# SparkFun_Noisy_Cricket.net
KiCad netlist of a schematic drawn in EAGLE
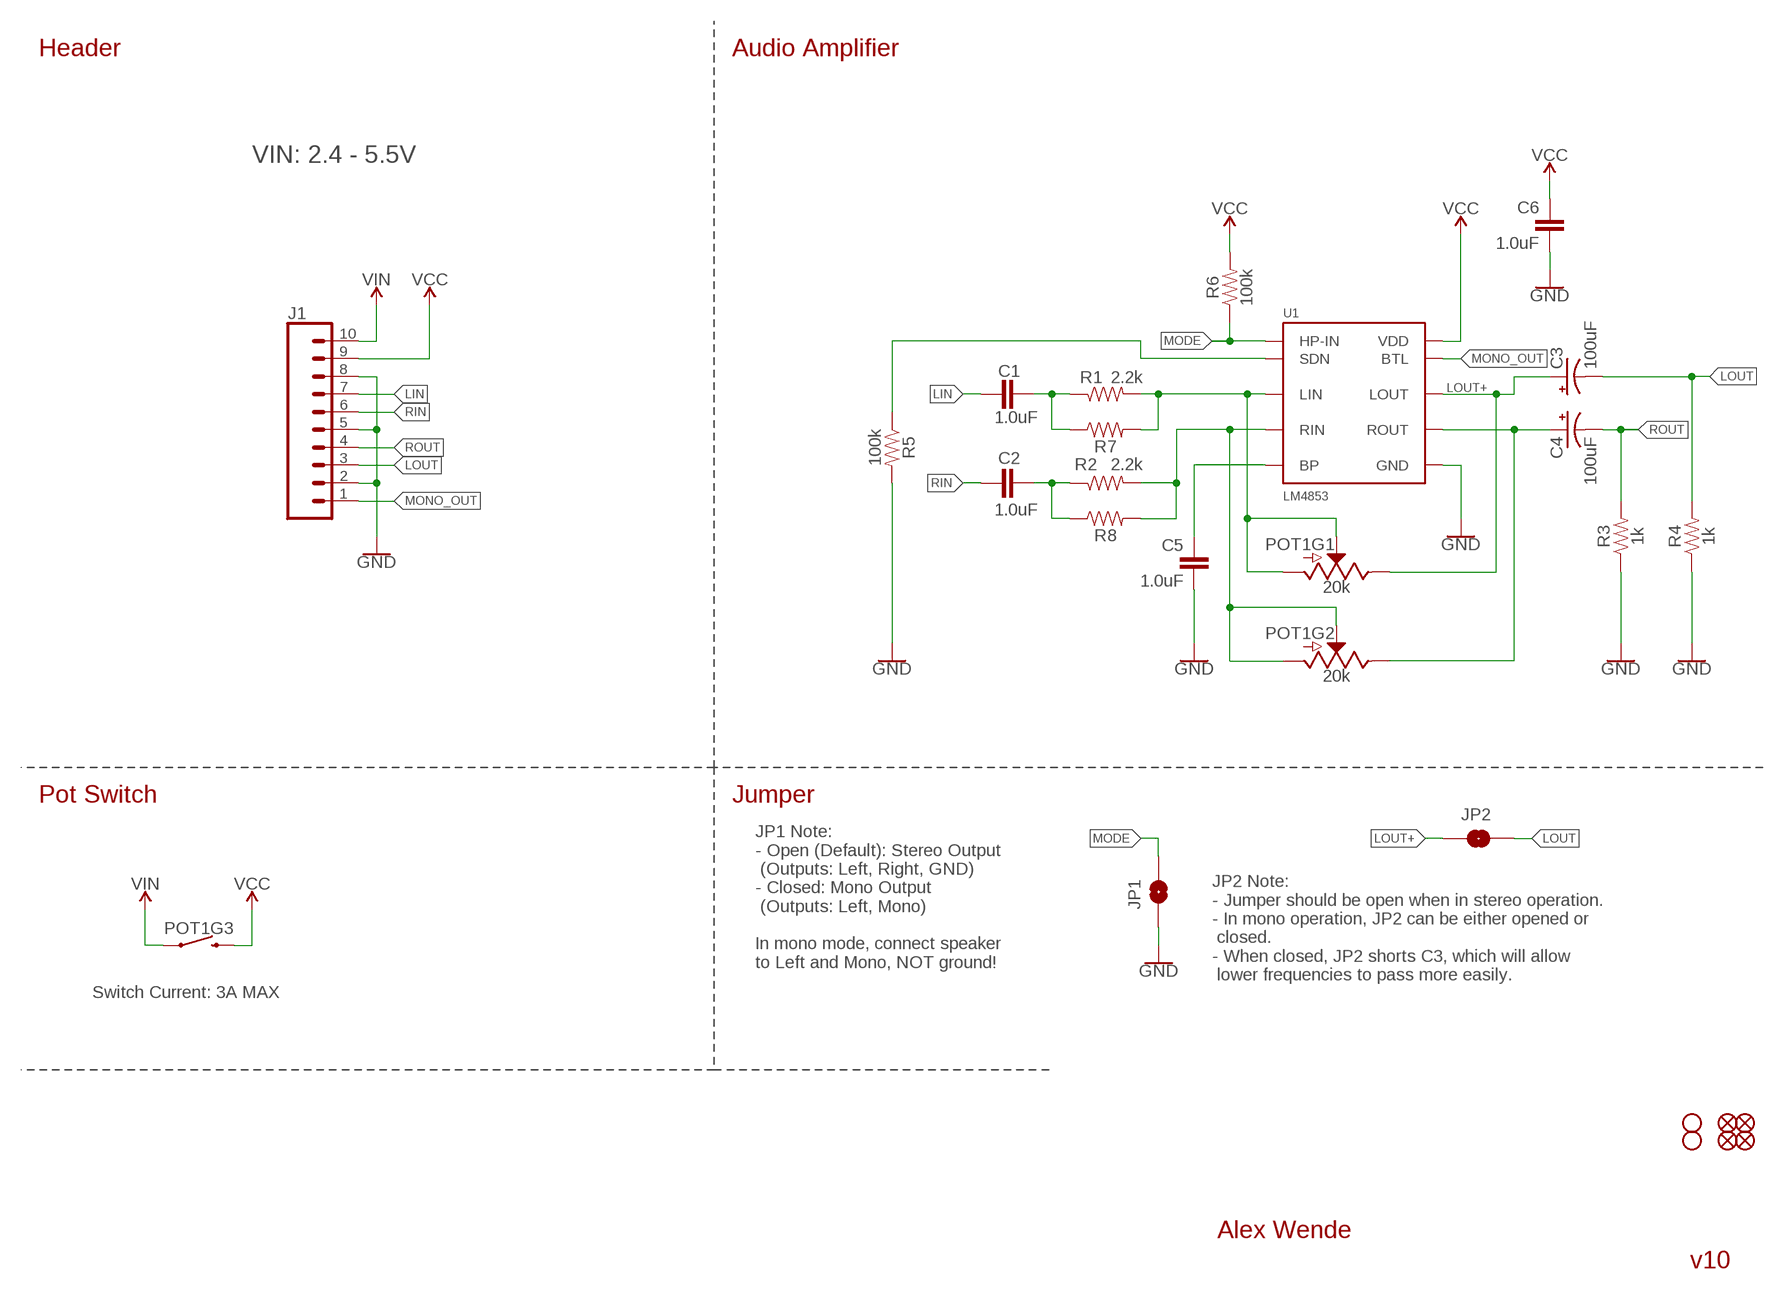
[diagram p0: schematic, sheet 1]

(export (version "E")
  (design (tool "Eeschema 10.0.6"))
  (components
    (comp (ref "C1")
      (value "1.0uF")
      (footprint "eagle-import:0603")
      (libsource (lib "eagle-import") (part "1.0UF-0603-16V-10%-X7R"))
    )
    (comp (ref "C2")
      (value "1.0uF")
      (footprint "eagle-import:0603")
      (libsource (lib "eagle-import") (part "1.0UF-0603-16V-10%-X7R"))
    )
    (comp (ref "C3")
      (value "100uF")
      (footprint "eagle-import:PANASONIC_D")
      (libsource (lib "eagle-import") (part "100UF-POLAR-25V-20%(ELEC)"))
    )
    (comp (ref "C4")
      (value "100uF")
      (footprint "eagle-import:PANASONIC_D")
      (libsource (lib "eagle-import") (part "100UF-POLAR-25V-20%(ELEC)"))
    )
    (comp (ref "C5")
      (value "1.0uF")
      (footprint "eagle-import:0603")
      (libsource (lib "eagle-import") (part "1.0UF-0603-16V-10%-X7R"))
    )
    (comp (ref "C6")
      (value "1.0uF")
      (footprint "eagle-import:0603")
      (libsource (lib "eagle-import") (part "1.0UF-0603-16V-10%-X7R"))
    )
    (comp (ref "FD1")
      (value "FIDUCIALUFIDUCIAL")
      (footprint "eagle-import:FIDUCIAL-MICRO")
      (libsource (lib "eagle-import") (part "FIDUCIALUFIDUCIAL"))
    )
    (comp (ref "FD2")
      (value "FIDUCIALUFIDUCIAL")
      (footprint "eagle-import:FIDUCIAL-MICRO")
      (libsource (lib "eagle-import") (part "FIDUCIALUFIDUCIAL"))
    )
    (comp (ref "FD3")
      (value "FIDUCIALUFIDUCIAL")
      (footprint "eagle-import:FIDUCIAL-MICRO")
      (libsource (lib "eagle-import") (part "FIDUCIALUFIDUCIAL"))
    )
    (comp (ref "FD4")
      (value "FIDUCIALUFIDUCIAL")
      (footprint "eagle-import:FIDUCIAL-MICRO")
      (libsource (lib "eagle-import") (part "FIDUCIALUFIDUCIAL"))
    )
    (comp (ref "H1")
      (value "STAND-OFF")
      (footprint "eagle-import:STAND-OFF")
      (libsource (lib "eagle-import") (part "STAND-OFF"))
    )
    (comp (ref "H2")
      (value "STAND-OFF")
      (footprint "eagle-import:STAND-OFF")
      (libsource (lib "eagle-import") (part "STAND-OFF"))
    )
    (comp (ref "J1")
      (value "CONN_10NO_SILK_PTH_FEMALE")
      (footprint "eagle-import:1X10_NO_SILK")
      (libsource (lib "eagle-import") (part "CONN_10NO_SILK_PTH_FEMALE"))
    )
    (comp (ref "JP1")
      (value "JUMPER-SMT_2_NO_NO-SILK")
      (footprint "eagle-import:SMT-JUMPER_2_NO_NO-SILK")
      (libsource (lib "eagle-import") (part "JUMPER-SMT_2_NO_NO-SILK"))
    )
    (comp (ref "JP2")
      (value "JUMPER-SMT_2_NO_NO-SILK")
      (footprint "eagle-import:SMT-JUMPER_2_NO_NO-SILK")
      (libsource (lib "eagle-import") (part "JUMPER-SMT_2_NO_NO-SILK"))
    )
    (comp (ref "POT1")
      (value "20k")
      (footprint "eagle-import:POT-DUAL-SWITCH-PTH")
      (libsource (lib "eagle-import") (part "POTENTIOMETER_DUAL_W/SWITCH"))
    )
    (comp (ref "R1")
      (value "2.2k")
      (footprint "eagle-import:0603")
      (libsource (lib "eagle-import") (part "2.2KOHM-0603-1/10W-1%"))
    )
    (comp (ref "R2")
      (value "2.2k")
      (footprint "eagle-import:0603")
      (libsource (lib "eagle-import") (part "2.2KOHM-0603-1/10W-1%"))
    )
    (comp (ref "R3")
      (value "1k")
      (footprint "eagle-import:0603")
      (libsource (lib "eagle-import") (part "1KOHM-0603-1/10W-1%"))
    )
    (comp (ref "R4")
      (value "1k")
      (footprint "eagle-import:0603")
      (libsource (lib "eagle-import") (part "1KOHM-0603-1/10W-1%"))
    )
    (comp (ref "R5")
      (value "100k")
      (footprint "eagle-import:0603")
      (libsource (lib "eagle-import") (part "100KOHM-0603-1/10W-1%"))
    )
    (comp (ref "R6")
      (value "100k")
      (footprint "eagle-import:0603")
      (libsource (lib "eagle-import") (part "100KOHM-0603-1/10W-1%"))
    )
    (comp (ref "R7")
      (value "RESISTORAXIAL-0.3-KIT")
      (footprint "eagle-import:AXIAL-0.3-KIT")
      (libsource (lib "eagle-import") (part "RESISTORAXIAL-0.3-KIT"))
    )
    (comp (ref "R8")
      (value "RESISTORAXIAL-0.3-KIT")
      (footprint "eagle-import:AXIAL-0.3-KIT")
      (libsource (lib "eagle-import") (part "RESISTORAXIAL-0.3-KIT"))
    )
    (comp (ref "U1")
      (value "LM4853")
      (footprint "eagle-import:TFSOP-10")
      (libsource (lib "eagle-import") (part "LM4853"))
    )
  )
  (nets
    (net (code "1") (name "GND") (class "Default")
      (node (ref "C5") (pin "2") (pinfunction "2_2") (pintype "passive"))
      (node (ref "C6") (pin "2") (pinfunction "2_2") (pintype "passive"))
      (node (ref "J1") (pin "2") (pinfunction "2_2") (pintype "passive"))
      (node (ref "J1") (pin "5") (pinfunction "5_5") (pintype "passive"))
      (node (ref "J1") (pin "8") (pinfunction "8_8") (pintype "passive"))
      (node (ref "JP1") (pin "1") (pinfunction "1_1") (pintype "passive"))
      (node (ref "R3") (pin "1") (pinfunction "1_1") (pintype "passive"))
      (node (ref "R4") (pin "1") (pinfunction "1_1") (pintype "passive"))
      (node (ref "R5") (pin "2") (pinfunction "2_2") (pintype "passive"))
      (node (ref "U1") (pin "GND") (pinfunction "GND_GND") (pintype "bidirectional"))
    )
    (net (code "2") (name "LIN") (class "Default")
      (node (ref "C1") (pin "1") (pinfunction "1_1") (pintype "passive"))
      (node (ref "J1") (pin "7") (pinfunction "7_7") (pintype "passive"))
    )
    (net (code "3") (name "LOUT") (class "Default")
      (node (ref "C3") (pin "-") (pinfunction "-_-") (pintype "passive"))
      (node (ref "J1") (pin "3") (pinfunction "3_3") (pintype "passive"))
      (node (ref "JP2") (pin "2") (pinfunction "2_2") (pintype "passive"))
      (node (ref "R4") (pin "2") (pinfunction "2_2") (pintype "passive"))
    )
    (net (code "4") (name "LOUT+") (class "Default")
      (node (ref "C3") (pin "+") (pinfunction "+_+") (pintype "passive"))
      (node (ref "JP2") (pin "1") (pinfunction "1_1") (pintype "passive"))
      (node (ref "POT1") (pin "A3") (pinfunction "E_A3") (pintype "passive"))
      (node (ref "U1") (pin "LOUT") (pinfunction "LOUT_LOUT") (pintype "bidirectional"))
    )
    (net (code "5") (name "MODE") (class "Default")
      (node (ref "JP1") (pin "2") (pinfunction "2_2") (pintype "passive"))
      (node (ref "R6") (pin "1") (pinfunction "1_1") (pintype "passive"))
      (node (ref "U1") (pin "HP-IN") (pinfunction "HP-IN_HP-IN") (pintype "bidirectional"))
    )
    (net (code "6") (name "MONO_OUT") (class "Default")
      (node (ref "J1") (pin "1") (pinfunction "1_1") (pintype "passive"))
      (node (ref "U1") (pin "BTL") (pinfunction "BTL_BTL") (pintype "bidirectional"))
    )
    (net (code "7") (name "Net-(C5-Pad1)") (class "Default")
      (node (ref "C5") (pin "1") (pinfunction "1_1") (pintype "passive"))
      (node (ref "U1") (pin "BP") (pinfunction "BP_BP") (pintype "bidirectional"))
    )
    (net (code "8") (name "Net-(POT1A-A)") (class "Default")
      (node (ref "POT1") (pin "A1") (pinfunction "A_A1") (pintype "passive"))
      (node (ref "POT1") (pin "A2") (pinfunction "S_A2") (pintype "passive"))
      (node (ref "R1") (pin "2") (pinfunction "2_2") (pintype "passive"))
      (node (ref "R7") (pin "P$2") (pinfunction "2_P$2") (pintype "passive"))
      (node (ref "U1") (pin "LIN") (pinfunction "LIN_LIN") (pintype "bidirectional"))
    )
    (net (code "9") (name "Net-(POT1B-A)") (class "Default")
      (node (ref "POT1") (pin "B1") (pinfunction "A_B1") (pintype "passive"))
      (node (ref "POT1") (pin "B2") (pinfunction "S_B2") (pintype "passive"))
      (node (ref "R2") (pin "2") (pinfunction "2_2") (pintype "passive"))
      (node (ref "R8") (pin "P$2") (pinfunction "2_P$2") (pintype "passive"))
      (node (ref "U1") (pin "RIN") (pinfunction "RIN_RIN") (pintype "bidirectional"))
    )
    (net (code "10") (name "Net-(POT1B-E)") (class "Default")
      (node (ref "C4") (pin "+") (pinfunction "+_+") (pintype "passive"))
      (node (ref "POT1") (pin "B3") (pinfunction "E_B3") (pintype "passive"))
      (node (ref "U1") (pin "ROUT") (pinfunction "ROUT_ROUT") (pintype "bidirectional"))
    )
    (net (code "11") (name "Net-(R5-Pad1)") (class "Default")
      (node (ref "R5") (pin "1") (pinfunction "1_1") (pintype "passive"))
      (node (ref "U1") (pin "SDN") (pinfunction "SDN_SDN") (pintype "bidirectional"))
    )
    (net (code "12") (name "Net-(R7-1)") (class "Default")
      (node (ref "C1") (pin "2") (pinfunction "2_2") (pintype "passive"))
      (node (ref "R1") (pin "1") (pinfunction "1_1") (pintype "passive"))
      (node (ref "R7") (pin "P$1") (pinfunction "1_P$1") (pintype "passive"))
    )
    (net (code "13") (name "Net-(R8-1)") (class "Default")
      (node (ref "C2") (pin "2") (pinfunction "2_2") (pintype "passive"))
      (node (ref "R2") (pin "1") (pinfunction "1_1") (pintype "passive"))
      (node (ref "R8") (pin "P$1") (pinfunction "1_P$1") (pintype "passive"))
    )
    (net (code "14") (name "RIN") (class "Default")
      (node (ref "C2") (pin "1") (pinfunction "1_1") (pintype "passive"))
      (node (ref "J1") (pin "6") (pinfunction "6_6") (pintype "passive"))
    )
    (net (code "15") (name "ROUT") (class "Default")
      (node (ref "C4") (pin "-") (pinfunction "-_-") (pintype "passive"))
      (node (ref "J1") (pin "4") (pinfunction "4_4") (pintype "passive"))
      (node (ref "R3") (pin "2") (pinfunction "2_2") (pintype "passive"))
    )
    (net (code "16") (name "VCC") (class "Default")
      (node (ref "C6") (pin "1") (pinfunction "1_1") (pintype "passive"))
      (node (ref "J1") (pin "9") (pinfunction "9_9") (pintype "passive"))
      (node (ref "POT1") (pin "SW2") (pinfunction "2_SW2") (pintype "passive"))
      (node (ref "R6") (pin "2") (pinfunction "2_2") (pintype "passive"))
      (node (ref "U1") (pin "VDD") (pinfunction "VDD_VDD") (pintype "bidirectional"))
    )
    (net (code "17") (name "VIN") (class "Default")
      (node (ref "J1") (pin "10") (pinfunction "10_10") (pintype "passive"))
      (node (ref "POT1") (pin "SW1") (pinfunction "1_SW1") (pintype "passive"))
    )
  )
)
